# deco_res.net
KiCad netlist of a schematic drawn in Altium Designer
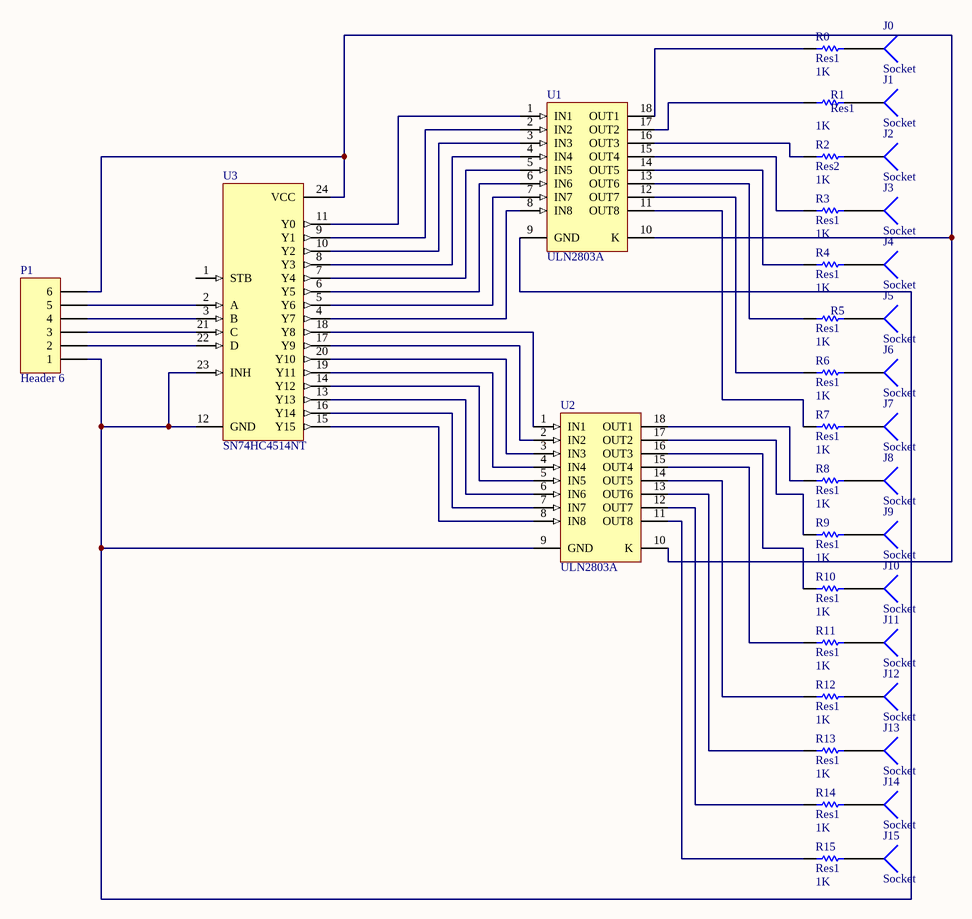
[diagram p0: deco+res.SchDoc]

(export (version "E")
  (design (tool "Eeschema 10.0.6"))
  (components
    (comp (ref "J0")
      (value "Socket")
      (footprint "PIN1")
      (fields (field (name "PUBLISHER") "Altium Limited"))
      (libsource (lib "Miscellaneous Connectors") (part "Socket"))
    )
    (comp (ref "J1")
      (value "Socket")
      (footprint "PIN1")
      (fields (field (name "PUBLISHER") "Altium Limited"))
      (libsource (lib "Miscellaneous Connectors") (part "Socket"))
    )
    (comp (ref "J2")
      (value "Socket")
      (footprint "PIN1")
      (fields (field (name "PUBLISHER") "Altium Limited"))
      (libsource (lib "Miscellaneous Connectors") (part "Socket"))
    )
    (comp (ref "J3")
      (value "Socket")
      (footprint "PIN1")
      (fields (field (name "PUBLISHER") "Altium Limited"))
      (libsource (lib "Miscellaneous Connectors") (part "Socket"))
    )
    (comp (ref "J4")
      (value "Socket")
      (footprint "PIN1")
      (fields (field (name "PUBLISHER") "Altium Limited"))
      (libsource (lib "Miscellaneous Connectors") (part "Socket"))
    )
    (comp (ref "J5")
      (value "Socket")
      (footprint "PIN1")
      (fields (field (name "PUBLISHER") "Altium Limited"))
      (libsource (lib "Miscellaneous Connectors") (part "Socket"))
    )
    (comp (ref "J6")
      (value "Socket")
      (footprint "PIN1")
      (fields (field (name "PUBLISHER") "Altium Limited"))
      (libsource (lib "Miscellaneous Connectors") (part "Socket"))
    )
    (comp (ref "J7")
      (value "Socket")
      (footprint "PIN1")
      (fields (field (name "PUBLISHER") "Altium Limited"))
      (libsource (lib "Miscellaneous Connectors") (part "Socket"))
    )
    (comp (ref "J8")
      (value "Socket")
      (footprint "PIN1")
      (fields (field (name "PUBLISHER") "Altium Limited"))
      (libsource (lib "Miscellaneous Connectors") (part "Socket"))
    )
    (comp (ref "J9")
      (value "Socket")
      (footprint "PIN1")
      (fields (field (name "PUBLISHER") "Altium Limited"))
      (libsource (lib "Miscellaneous Connectors") (part "Socket"))
    )
    (comp (ref "J10")
      (value "Socket")
      (footprint "PIN1")
      (fields (field (name "PUBLISHER") "Altium Limited"))
      (libsource (lib "Miscellaneous Connectors") (part "Socket"))
    )
    (comp (ref "J11")
      (value "Socket")
      (footprint "PIN1")
      (fields (field (name "PUBLISHER") "Altium Limited"))
      (libsource (lib "Miscellaneous Connectors") (part "Socket"))
    )
    (comp (ref "J12")
      (value "Socket")
      (footprint "PIN1")
      (fields (field (name "PUBLISHER") "Altium Limited"))
      (libsource (lib "Miscellaneous Connectors") (part "Socket"))
    )
    (comp (ref "J13")
      (value "Socket")
      (footprint "PIN1")
      (fields (field (name "PUBLISHER") "Altium Limited"))
      (libsource (lib "Miscellaneous Connectors") (part "Socket"))
    )
    (comp (ref "J14")
      (value "Socket")
      (footprint "PIN1")
      (fields (field (name "PUBLISHER") "Altium Limited"))
      (libsource (lib "Miscellaneous Connectors") (part "Socket"))
    )
    (comp (ref "J15")
      (value "Socket")
      (footprint "PIN1")
      (fields (field (name "PUBLISHER") "Altium Limited"))
      (libsource (lib "Miscellaneous Connectors") (part "Socket"))
    )
    (comp (ref "P1")
      (value "Header 6")
      (footprint "HDR1X6")
      (description "Header, 6-Pin")
      (fields (field (name "PUBLISHER") "Altium Limited"))
      (libsource (lib "Miscellaneous Connectors") (part "Header 6"))
    )
    (comp (ref "R0")
      (value "Res1")
      (footprint "AXIAL-0.3")
      (description "Resistor")
      (fields (field (name "ALTIUM_VALUE") "1K") (field (name "PUBLISHER") "Altium Limited"))
      (libsource (lib "Miscellaneous Devices") (part "Res1"))
    )
    (comp (ref "R1")
      (value "Res1")
      (footprint "AXIAL-0.3")
      (description "Resistor")
      (fields (field (name "ALTIUM_VALUE") "1K") (field (name "PUBLISHER") "Altium Limited"))
      (libsource (lib "Miscellaneous Devices") (part "Res1"))
    )
    (comp (ref "R2")
      (value "Res2")
      (footprint "AXIAL-0.3")
      (description "Resistor")
      (fields (field (name "ALTIUM_VALUE") "1K") (field (name "PUBLISHER") "Altium Limited"))
      (libsource (lib "Miscellaneous Devices") (part "Res1"))
    )
    (comp (ref "R3")
      (value "Res1")
      (footprint "AXIAL-0.3")
      (description "Resistor")
      (fields (field (name "ALTIUM_VALUE") "1K") (field (name "PUBLISHER") "Altium Limited"))
      (libsource (lib "Miscellaneous Devices") (part "Res1"))
    )
    (comp (ref "R4")
      (value "Res1")
      (footprint "AXIAL-0.3")
      (description "Resistor")
      (fields (field (name "ALTIUM_VALUE") "1K") (field (name "PUBLISHER") "Altium Limited"))
      (libsource (lib "Miscellaneous Devices") (part "Res1"))
    )
    (comp (ref "R5")
      (value "Res1")
      (footprint "AXIAL-0.3")
      (description "Resistor")
      (fields (field (name "ALTIUM_VALUE") "1K") (field (name "PUBLISHER") "Altium Limited"))
      (libsource (lib "Miscellaneous Devices") (part "Res1"))
    )
    (comp (ref "R6")
      (value "Res1")
      (footprint "AXIAL-0.3")
      (description "Resistor")
      (fields (field (name "ALTIUM_VALUE") "1K") (field (name "PUBLISHER") "Altium Limited"))
      (libsource (lib "Miscellaneous Devices") (part "Res1"))
    )
    (comp (ref "R7")
      (value "Res1")
      (footprint "AXIAL-0.3")
      (description "Resistor")
      (fields (field (name "ALTIUM_VALUE") "1K") (field (name "PUBLISHER") "Altium Limited"))
      (libsource (lib "Miscellaneous Devices") (part "Res1"))
    )
    (comp (ref "R8")
      (value "Res1")
      (footprint "AXIAL-0.3")
      (description "Resistor")
      (fields (field (name "ALTIUM_VALUE") "1K") (field (name "PUBLISHER") "Altium Limited"))
      (libsource (lib "Miscellaneous Devices") (part "Res1"))
    )
    (comp (ref "R9")
      (value "Res1")
      (footprint "AXIAL-0.3")
      (description "Resistor")
      (fields (field (name "ALTIUM_VALUE") "1K") (field (name "PUBLISHER") "Altium Limited"))
      (libsource (lib "Miscellaneous Devices") (part "Res1"))
    )
    (comp (ref "R10")
      (value "Res1")
      (footprint "AXIAL-0.3")
      (description "Resistor")
      (fields (field (name "ALTIUM_VALUE") "1K") (field (name "PUBLISHER") "Altium Limited"))
      (libsource (lib "Miscellaneous Devices") (part "Res1"))
    )
    (comp (ref "R11")
      (value "Res1")
      (footprint "AXIAL-0.3")
      (description "Resistor")
      (fields (field (name "ALTIUM_VALUE") "1K") (field (name "PUBLISHER") "Altium Limited"))
      (libsource (lib "Miscellaneous Devices") (part "Res1"))
    )
    (comp (ref "R12")
      (value "Res1")
      (footprint "AXIAL-0.3")
      (description "Resistor")
      (fields (field (name "ALTIUM_VALUE") "1K") (field (name "PUBLISHER") "Altium Limited"))
      (libsource (lib "Miscellaneous Devices") (part "Res1"))
    )
    (comp (ref "R13")
      (value "Res1")
      (footprint "AXIAL-0.3")
      (description "Resistor")
      (fields (field (name "ALTIUM_VALUE") "1K") (field (name "PUBLISHER") "Altium Limited"))
      (libsource (lib "Miscellaneous Devices") (part "Res1"))
    )
    (comp (ref "R14")
      (value "Res1")
      (footprint "AXIAL-0.3")
      (description "Resistor")
      (fields (field (name "ALTIUM_VALUE") "1K") (field (name "PUBLISHER") "Altium Limited"))
      (libsource (lib "Miscellaneous Devices") (part "Res1"))
    )
    (comp (ref "R15")
      (value "Res1")
      (footprint "AXIAL-0.3")
      (description "Resistor")
      (fields (field (name "ALTIUM_VALUE") "1K") (field (name "PUBLISHER") "Altium Limited"))
      (libsource (lib "Miscellaneous Devices") (part "Res1"))
    )
    (comp (ref "U1")
      (value "ULN2803A")
      (footprint "707-02")
      (description "Octal Peripheral Driver Array")
      (fields (field (name "PUBLISHER") "Altium Limited"))
      (libsource (lib "Motorola Interface Peripheral Driver") (part "ULN2803A"))
    )
    (comp (ref "U2")
      (value "ULN2803A")
      (footprint "707-02")
      (description "Octal Peripheral Driver Array")
      (fields (field (name "PUBLISHER") "Altium Limited"))
      (libsource (lib "Motorola Interface Peripheral Driver") (part "ULN2803A"))
    )
    (comp (ref "U3")
      (value "SN74HC4514NT")
      (footprint "NT024")
      (description "4-Line to 16-Line Decoder / Demultiplexer with Address Latches")
      (fields (field (name "PUBLISHER") "Altium Limited"))
      (libsource (lib "TI Logic Decoder Demux") (part "SN74HC4514NT"))
    )
  )
  (nets
    (net (code "1") (name "Net-(J0-Pad1)") (class "Default")
      (node (ref "J0") (pin "1") (pinfunction "1_1") (pintype "passive"))
      (node (ref "R0") (pin "2") (pinfunction "2_2") (pintype "passive"))
    )
    (net (code "2") (name "Net-(J1-Pad1)") (class "Default")
      (node (ref "J1") (pin "1") (pinfunction "1_1") (pintype "passive"))
      (node (ref "R1") (pin "2") (pinfunction "2_2") (pintype "passive"))
    )
    (net (code "3") (name "Net-(J2-Pad1)") (class "Default")
      (node (ref "J2") (pin "1") (pinfunction "1_1") (pintype "passive"))
      (node (ref "R2") (pin "2") (pinfunction "2_2") (pintype "passive"))
    )
    (net (code "4") (name "Net-(J3-Pad1)") (class "Default")
      (node (ref "J3") (pin "1") (pinfunction "1_1") (pintype "passive"))
      (node (ref "R3") (pin "2") (pinfunction "2_2") (pintype "passive"))
    )
    (net (code "5") (name "Net-(J4-Pad1)") (class "Default")
      (node (ref "J4") (pin "1") (pinfunction "1_1") (pintype "passive"))
      (node (ref "R4") (pin "2") (pinfunction "2_2") (pintype "passive"))
    )
    (net (code "6") (name "Net-(J5-Pad1)") (class "Default")
      (node (ref "J5") (pin "1") (pinfunction "1_1") (pintype "passive"))
      (node (ref "R5") (pin "2") (pinfunction "2_2") (pintype "passive"))
    )
    (net (code "7") (name "Net-(J6-Pad1)") (class "Default")
      (node (ref "J6") (pin "1") (pinfunction "1_1") (pintype "passive"))
      (node (ref "R6") (pin "2") (pinfunction "2_2") (pintype "passive"))
    )
    (net (code "8") (name "Net-(J7-Pad1)") (class "Default")
      (node (ref "J7") (pin "1") (pinfunction "1_1") (pintype "passive"))
      (node (ref "R7") (pin "2") (pinfunction "2_2") (pintype "passive"))
    )
    (net (code "9") (name "Net-(J8-Pad1)") (class "Default")
      (node (ref "J8") (pin "1") (pinfunction "1_1") (pintype "passive"))
      (node (ref "R8") (pin "2") (pinfunction "2_2") (pintype "passive"))
    )
    (net (code "10") (name "Net-(J9-Pad1)") (class "Default")
      (node (ref "J9") (pin "1") (pinfunction "1_1") (pintype "passive"))
      (node (ref "R9") (pin "2") (pinfunction "2_2") (pintype "passive"))
    )
    (net (code "11") (name "Net-(J10-Pad1)") (class "Default")
      (node (ref "J10") (pin "1") (pinfunction "1_1") (pintype "passive"))
      (node (ref "R10") (pin "2") (pinfunction "2_2") (pintype "passive"))
    )
    (net (code "12") (name "Net-(J11-Pad1)") (class "Default")
      (node (ref "J11") (pin "1") (pinfunction "1_1") (pintype "passive"))
      (node (ref "R11") (pin "2") (pinfunction "2_2") (pintype "passive"))
    )
    (net (code "13") (name "Net-(J12-Pad1)") (class "Default")
      (node (ref "J12") (pin "1") (pinfunction "1_1") (pintype "passive"))
      (node (ref "R12") (pin "2") (pinfunction "2_2") (pintype "passive"))
    )
    (net (code "14") (name "Net-(J13-Pad1)") (class "Default")
      (node (ref "J13") (pin "1") (pinfunction "1_1") (pintype "passive"))
      (node (ref "R13") (pin "2") (pinfunction "2_2") (pintype "passive"))
    )
    (net (code "15") (name "Net-(J14-Pad1)") (class "Default")
      (node (ref "J14") (pin "1") (pinfunction "1_1") (pintype "passive"))
      (node (ref "R14") (pin "2") (pinfunction "2_2") (pintype "passive"))
    )
    (net (code "16") (name "Net-(J15-Pad1)") (class "Default")
      (node (ref "J15") (pin "1") (pinfunction "1_1") (pintype "passive"))
      (node (ref "R15") (pin "2") (pinfunction "2_2") (pintype "passive"))
    )
    (net (code "17") (name "Net-(U1-GND)") (class "Default")
      (node (ref "P1") (pin "1") (pinfunction "1_1") (pintype "passive"))
      (node (ref "U1") (pin "9") (pinfunction "GND_9") (pintype "power_in"))
      (node (ref "U2") (pin "9") (pinfunction "GND_9") (pintype "power_in"))
      (node (ref "U3") (pin "12") (pinfunction "GND_12") (pintype "power_in"))
      (node (ref "U3") (pin "23") (pinfunction "INH_23") (pintype "input"))
    )
    (net (code "18") (name "Net-(U1-IN1)") (class "Default")
      (node (ref "U1") (pin "1") (pinfunction "IN1_1") (pintype "input"))
      (node (ref "U3") (pin "11") (pinfunction "Y0_11") (pintype "output"))
    )
    (net (code "19") (name "Net-(U1-IN2)") (class "Default")
      (node (ref "U1") (pin "2") (pinfunction "IN2_2") (pintype "input"))
      (node (ref "U3") (pin "9") (pinfunction "Y1_9") (pintype "output"))
    )
    (net (code "20") (name "Net-(U1-IN3)") (class "Default")
      (node (ref "U1") (pin "3") (pinfunction "IN3_3") (pintype "input"))
      (node (ref "U3") (pin "10") (pinfunction "Y2_10") (pintype "output"))
    )
    (net (code "21") (name "Net-(U1-IN4)") (class "Default")
      (node (ref "U1") (pin "4") (pinfunction "IN4_4") (pintype "input"))
      (node (ref "U3") (pin "8") (pinfunction "Y3_8") (pintype "output"))
    )
    (net (code "22") (name "Net-(U1-IN5)") (class "Default")
      (node (ref "U1") (pin "5") (pinfunction "IN5_5") (pintype "input"))
      (node (ref "U3") (pin "7") (pinfunction "Y4_7") (pintype "output"))
    )
    (net (code "23") (name "Net-(U1-IN6)") (class "Default")
      (node (ref "U1") (pin "6") (pinfunction "IN6_6") (pintype "input"))
      (node (ref "U3") (pin "6") (pinfunction "Y5_6") (pintype "output"))
    )
    (net (code "24") (name "Net-(U1-IN7)") (class "Default")
      (node (ref "U1") (pin "7") (pinfunction "IN7_7") (pintype "input"))
      (node (ref "U3") (pin "5") (pinfunction "Y6_5") (pintype "output"))
    )
    (net (code "25") (name "Net-(U1-IN8)") (class "Default")
      (node (ref "U1") (pin "8") (pinfunction "IN8_8") (pintype "input"))
      (node (ref "U3") (pin "4") (pinfunction "Y7_4") (pintype "output"))
    )
    (net (code "26") (name "Net-(U1-K)") (class "Default")
      (node (ref "P1") (pin "6") (pinfunction "6_6") (pintype "passive"))
      (node (ref "U1") (pin "10") (pinfunction "K_10") (pintype "passive"))
      (node (ref "U2") (pin "10") (pinfunction "K_10") (pintype "passive"))
      (node (ref "U3") (pin "24") (pinfunction "VCC_24") (pintype "power_in"))
    )
    (net (code "27") (name "Net-(U1-OUT1)") (class "Default")
      (node (ref "R0") (pin "1") (pinfunction "1_1") (pintype "passive"))
      (node (ref "U1") (pin "18") (pinfunction "OUT1_18") (pintype "open_collector"))
    )
    (net (code "28") (name "Net-(U1-OUT2)") (class "Default")
      (node (ref "R1") (pin "1") (pinfunction "1_1") (pintype "passive"))
      (node (ref "U1") (pin "17") (pinfunction "OUT2_17") (pintype "open_collector"))
    )
    (net (code "29") (name "Net-(U1-OUT3)") (class "Default")
      (node (ref "R2") (pin "1") (pinfunction "1_1") (pintype "passive"))
      (node (ref "U1") (pin "16") (pinfunction "OUT3_16") (pintype "open_collector"))
    )
    (net (code "30") (name "Net-(U1-OUT4)") (class "Default")
      (node (ref "R3") (pin "1") (pinfunction "1_1") (pintype "passive"))
      (node (ref "U1") (pin "15") (pinfunction "OUT4_15") (pintype "open_collector"))
    )
    (net (code "31") (name "Net-(U1-OUT5)") (class "Default")
      (node (ref "R4") (pin "1") (pinfunction "1_1") (pintype "passive"))
      (node (ref "U1") (pin "14") (pinfunction "OUT5_14") (pintype "open_collector"))
    )
    (net (code "32") (name "Net-(U1-OUT6)") (class "Default")
      (node (ref "R5") (pin "1") (pinfunction "1_1") (pintype "passive"))
      (node (ref "U1") (pin "13") (pinfunction "OUT6_13") (pintype "open_collector"))
    )
    (net (code "33") (name "Net-(U1-OUT7)") (class "Default")
      (node (ref "R6") (pin "1") (pinfunction "1_1") (pintype "passive"))
      (node (ref "U1") (pin "12") (pinfunction "OUT7_12") (pintype "open_collector"))
    )
    (net (code "34") (name "Net-(U1-OUT8)") (class "Default")
      (node (ref "R7") (pin "1") (pinfunction "1_1") (pintype "passive"))
      (node (ref "U1") (pin "11") (pinfunction "OUT8_11") (pintype "open_collector"))
    )
    (net (code "35") (name "Net-(U2-IN1)") (class "Default")
      (node (ref "U2") (pin "1") (pinfunction "IN1_1") (pintype "input"))
      (node (ref "U3") (pin "18") (pinfunction "Y8_18") (pintype "output"))
    )
    (net (code "36") (name "Net-(U2-IN2)") (class "Default")
      (node (ref "U2") (pin "2") (pinfunction "IN2_2") (pintype "input"))
      (node (ref "U3") (pin "17") (pinfunction "Y9_17") (pintype "output"))
    )
    (net (code "37") (name "Net-(U2-IN3)") (class "Default")
      (node (ref "U2") (pin "3") (pinfunction "IN3_3") (pintype "input"))
      (node (ref "U3") (pin "20") (pinfunction "Y10_20") (pintype "output"))
    )
    (net (code "38") (name "Net-(U2-IN4)") (class "Default")
      (node (ref "U2") (pin "4") (pinfunction "IN4_4") (pintype "input"))
      (node (ref "U3") (pin "19") (pinfunction "Y11_19") (pintype "output"))
    )
    (net (code "39") (name "Net-(U2-IN5)") (class "Default")
      (node (ref "U2") (pin "5") (pinfunction "IN5_5") (pintype "input"))
      (node (ref "U3") (pin "14") (pinfunction "Y12_14") (pintype "output"))
    )
    (net (code "40") (name "Net-(U2-IN6)") (class "Default")
      (node (ref "U2") (pin "6") (pinfunction "IN6_6") (pintype "input"))
      (node (ref "U3") (pin "13") (pinfunction "Y13_13") (pintype "output"))
    )
    (net (code "41") (name "Net-(U2-IN7)") (class "Default")
      (node (ref "U2") (pin "7") (pinfunction "IN7_7") (pintype "input"))
      (node (ref "U3") (pin "16") (pinfunction "Y14_16") (pintype "output"))
    )
    (net (code "42") (name "Net-(U2-IN8)") (class "Default")
      (node (ref "U2") (pin "8") (pinfunction "IN8_8") (pintype "input"))
      (node (ref "U3") (pin "15") (pinfunction "Y15_15") (pintype "output"))
    )
    (net (code "43") (name "Net-(U2-OUT1)") (class "Default")
      (node (ref "R8") (pin "1") (pinfunction "1_1") (pintype "passive"))
      (node (ref "U2") (pin "18") (pinfunction "OUT1_18") (pintype "open_collector"))
    )
    (net (code "44") (name "Net-(U2-OUT2)") (class "Default")
      (node (ref "R9") (pin "1") (pinfunction "1_1") (pintype "passive"))
      (node (ref "U2") (pin "17") (pinfunction "OUT2_17") (pintype "open_collector"))
    )
    (net (code "45") (name "Net-(U2-OUT3)") (class "Default")
      (node (ref "R10") (pin "1") (pinfunction "1_1") (pintype "passive"))
      (node (ref "U2") (pin "16") (pinfunction "OUT3_16") (pintype "open_collector"))
    )
    (net (code "46") (name "Net-(U2-OUT4)") (class "Default")
      (node (ref "R11") (pin "1") (pinfunction "1_1") (pintype "passive"))
      (node (ref "U2") (pin "15") (pinfunction "OUT4_15") (pintype "open_collector"))
    )
    (net (code "47") (name "Net-(U2-OUT5)") (class "Default")
      (node (ref "R12") (pin "1") (pinfunction "1_1") (pintype "passive"))
      (node (ref "U2") (pin "14") (pinfunction "OUT5_14") (pintype "open_collector"))
    )
    (net (code "48") (name "Net-(U2-OUT6)") (class "Default")
      (node (ref "R13") (pin "1") (pinfunction "1_1") (pintype "passive"))
      (node (ref "U2") (pin "13") (pinfunction "OUT6_13") (pintype "open_collector"))
    )
    (net (code "49") (name "Net-(U2-OUT7)") (class "Default")
      (node (ref "R14") (pin "1") (pinfunction "1_1") (pintype "passive"))
      (node (ref "U2") (pin "12") (pinfunction "OUT7_12") (pintype "open_collector"))
    )
    (net (code "50") (name "Net-(U2-OUT8)") (class "Default")
      (node (ref "R15") (pin "1") (pinfunction "1_1") (pintype "passive"))
      (node (ref "U2") (pin "11") (pinfunction "OUT8_11") (pintype "open_collector"))
    )
    (net (code "51") (name "Net-(U3-A)") (class "Default")
      (node (ref "P1") (pin "5") (pinfunction "5_5") (pintype "passive"))
      (node (ref "U3") (pin "2") (pinfunction "A_2") (pintype "input"))
    )
    (net (code "52") (name "Net-(U3-B)") (class "Default")
      (node (ref "P1") (pin "4") (pinfunction "4_4") (pintype "passive"))
      (node (ref "U3") (pin "3") (pinfunction "B_3") (pintype "input"))
    )
    (net (code "53") (name "Net-(U3-C)") (class "Default")
      (node (ref "P1") (pin "3") (pinfunction "3_3") (pintype "passive"))
      (node (ref "U3") (pin "21") (pinfunction "C_21") (pintype "input"))
    )
    (net (code "54") (name "Net-(U3-D)") (class "Default")
      (node (ref "P1") (pin "2") (pinfunction "2_2") (pintype "passive"))
      (node (ref "U3") (pin "22") (pinfunction "D_22") (pintype "input"))
    )
    (net (code "55") (name "unconnected-(U3-STB-Pad1)") (class "Default")
      (node (ref "U3") (pin "1") (pinfunction "STB_1") (pintype "input"))
    )
  )
)
